# TrinketTrigger.net
KiCad netlist of a schematic drawn in EAGLE
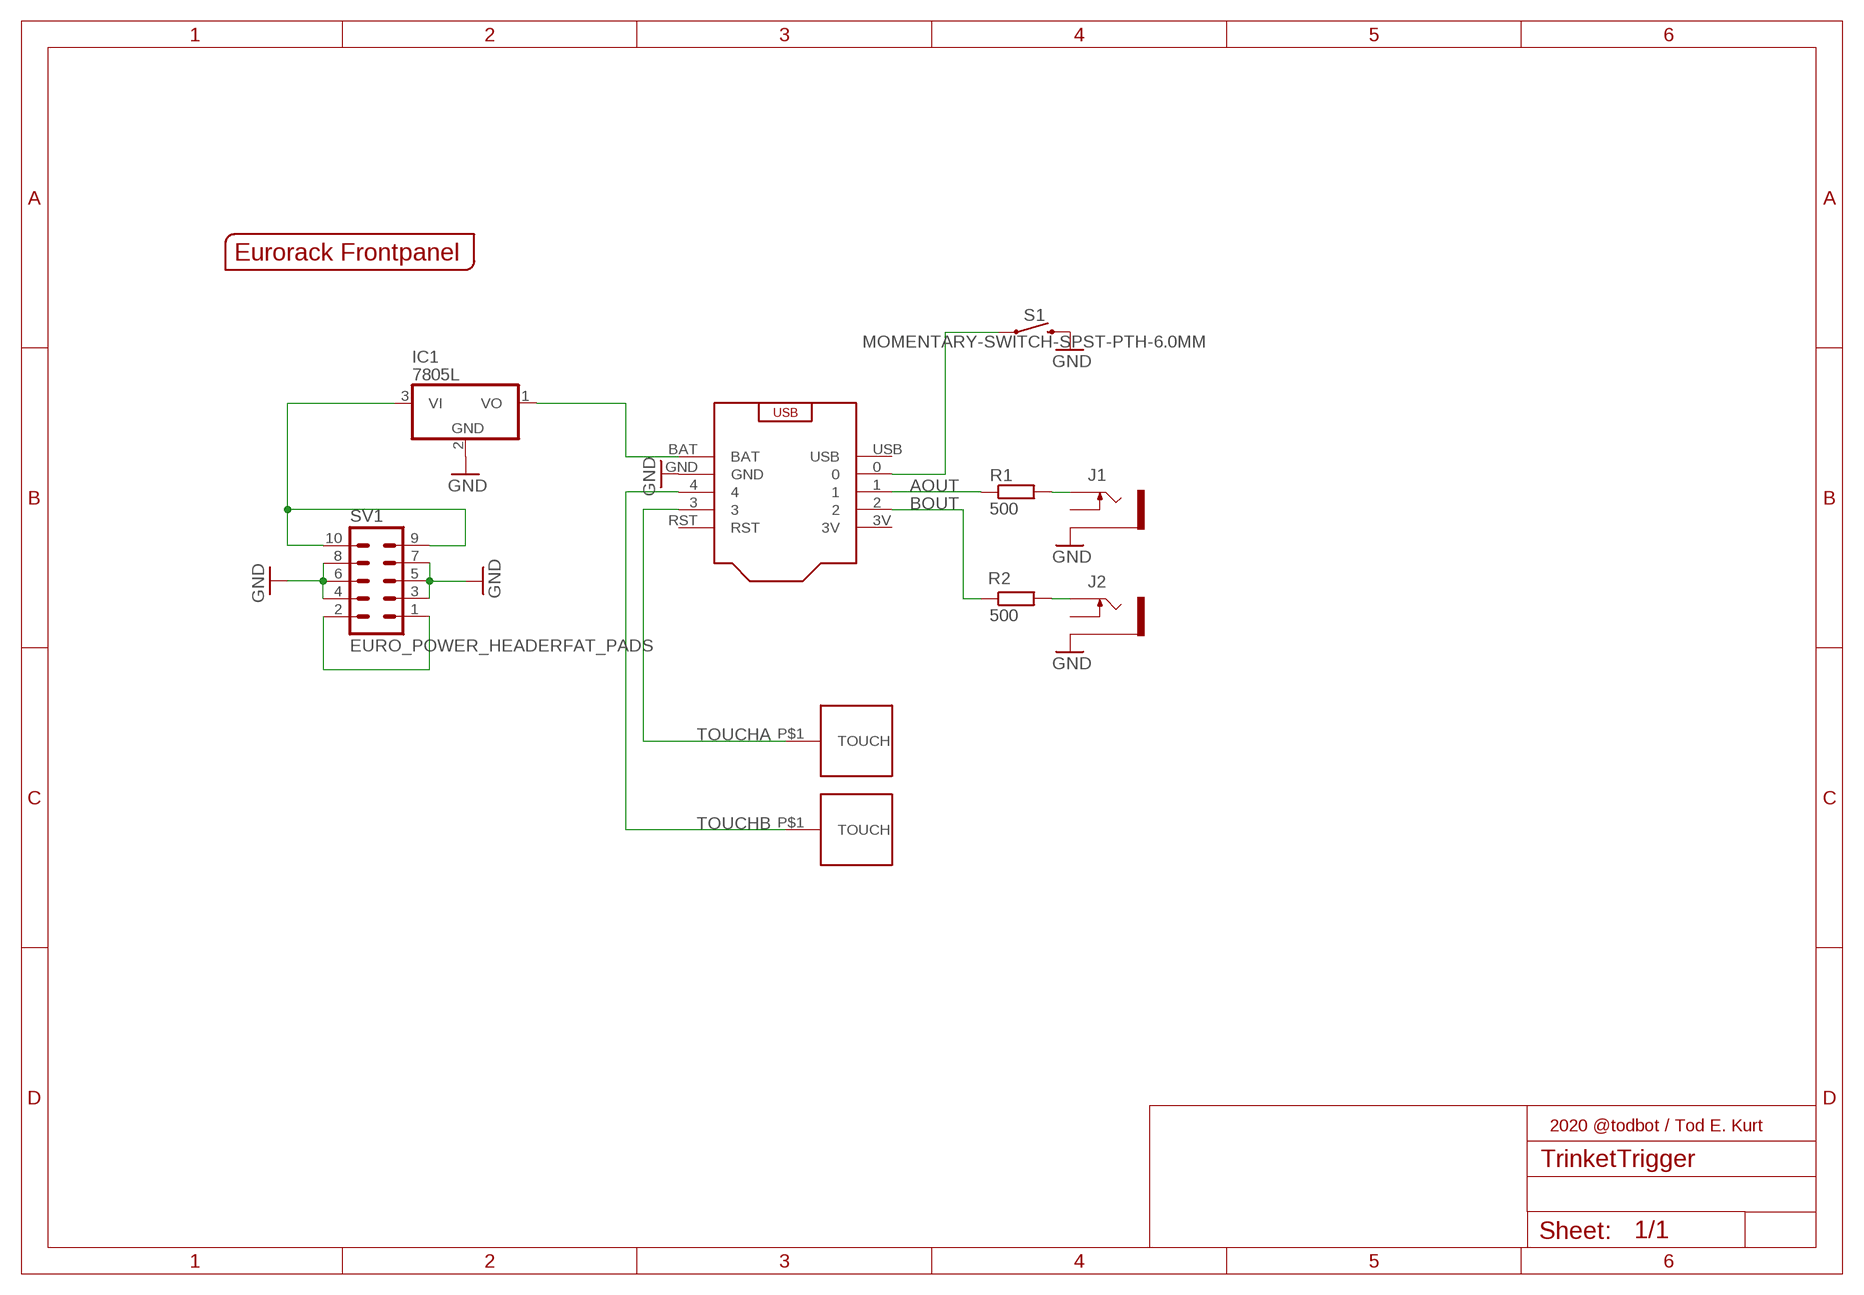
[diagram p0: schematic, sheet 1]

(export (version "E")
  (design (tool "Eeschema 10.0.6"))
  (components
    (comp (ref "IC1")
      (value "7805L")
      (footprint "eagle-import:TO92")
      (libsource (lib "eagle-import") (part "78L05"))
    )
    (comp (ref "J1")
      (value "THONKICONNNEW")
      (footprint "eagle-import:WQP-PJ301M-12_JACK")
      (libsource (lib "eagle-import") (part "THONKICONNNEW"))
    )
    (comp (ref "J2")
      (value "THONKICONNNEW")
      (footprint "eagle-import:WQP-PJ301M-12_JACK")
      (libsource (lib "eagle-import") (part "THONKICONNNEW"))
    )
    (comp (ref "R1")
      (value "500")
      (footprint "eagle-import:0204_7")
      (libsource (lib "eagle-import") (part "R-EU_0204/7"))
    )
    (comp (ref "R2")
      (value "500")
      (footprint "eagle-import:0204_7")
      (libsource (lib "eagle-import") (part "R-EU_0204/7"))
    )
    (comp (ref "S1")
      (value "MOMENTARY-SWITCH-SPST-PTH-6.0MM")
      (footprint "eagle-import:TACTILE_SWITCH_PTH_6.0MM")
      (libsource (lib "eagle-import") (part "MOMENTARY-SWITCH-SPST-PTH-6.0MM"))
    )
    (comp (ref "SV1")
      (value "EURO_POWER_HEADERFAT_PADS")
      (footprint "eagle-import:EURO_PWR_HEADER_FAT")
      (libsource (lib "eagle-import") (part "EURO_POWER_HEADERFAT_PADS"))
    )
    (comp (ref "TOUCHA")
      (value "TOUCHPADA")
      (footprint "eagle-import:TOUCHPADA")
      (libsource (lib "eagle-import") (part "TOUCHPADA"))
    )
    (comp (ref "TOUCHB")
      (value "TOUCHPADA")
      (footprint "eagle-import:TOUCHPADA")
      (libsource (lib "eagle-import") (part "TOUCHPADA"))
    )
    (comp (ref "U$1")
      (value "EURORACK_PANEL6HP")
      (footprint "eagle-import:EURORACK6HPPANEL")
      (libsource (lib "eagle-import") (part "EURORACK_PANEL6HP"))
    )
    (comp (ref "U$2")
      (value "TRINKETM0NH")
      (footprint "eagle-import:TRINKETMO_NOHOLES")
      (libsource (lib "eagle-import") (part "TRINKETM0NH"))
    )
  )
  (nets
    (net (code "1") (name "/AOUT") (class "Default")
      (node (ref "R1") (pin "1") (pinfunction "1_1") (pintype "passive"))
      (node (ref "U$2") (pin "1") (pinfunction "1_1") (pintype "bidirectional"))
    )
    (net (code "2") (name "/BOUT") (class "Default")
      (node (ref "R2") (pin "1") (pinfunction "1_1") (pintype "passive"))
      (node (ref "U$2") (pin "2") (pinfunction "2_2") (pintype "bidirectional"))
    )
    (net (code "3") (name "/TOUCHA") (class "Default")
      (node (ref "TOUCHA") (pin "P$1") (pinfunction "TOUCH_P$1") (pintype "bidirectional"))
      (node (ref "U$2") (pin "3") (pinfunction "3_3") (pintype "bidirectional"))
    )
    (net (code "4") (name "/TOUCHB") (class "Default")
      (node (ref "TOUCHB") (pin "P$1") (pinfunction "TOUCH_P$1") (pintype "bidirectional"))
      (node (ref "U$2") (pin "4") (pinfunction "4_4") (pintype "bidirectional"))
    )
    (net (code "5") (name "GND") (class "Default")
      (node (ref "IC1") (pin "2") (pinfunction "GND_2") (pintype "passive"))
      (node (ref "J1") (pin "P$3_SLEEVE") (pinfunction "SLEEVE_P$3_SLEEVE") (pintype "passive"))
      (node (ref "J2") (pin "P$3_SLEEVE") (pinfunction "SLEEVE_P$3_SLEEVE") (pintype "passive"))
      (node (ref "S1") (pin "3") (pinfunction "2_3") (pintype "passive"))
      (node (ref "SV1") (pin "3") (pinfunction "3_3") (pintype "passive"))
      (node (ref "SV1") (pin "4") (pinfunction "4_4") (pintype "passive"))
      (node (ref "SV1") (pin "5") (pinfunction "5_5") (pintype "passive"))
      (node (ref "SV1") (pin "6") (pinfunction "6_6") (pintype "passive"))
      (node (ref "SV1") (pin "7") (pinfunction "7_7") (pintype "passive"))
      (node (ref "SV1") (pin "8") (pinfunction "8_8") (pintype "passive"))
      (node (ref "U$2") (pin "GND") (pinfunction "GND_GND") (pintype "bidirectional"))
    )
    (net (code "6") (name "Net-(IC1-VI)") (class "Default")
      (node (ref "IC1") (pin "3") (pinfunction "VI_3") (pintype "input"))
      (node (ref "SV1") (pin "10") (pinfunction "10_10") (pintype "passive"))
      (node (ref "SV1") (pin "9") (pinfunction "9_9") (pintype "passive"))
    )
    (net (code "7") (name "Net-(IC1-VO)") (class "Default")
      (node (ref "IC1") (pin "1") (pinfunction "VO_1") (pintype "passive"))
      (node (ref "U$2") (pin "BAT") (pinfunction "BAT_BAT") (pintype "bidirectional"))
    )
    (net (code "8") (name "Net-(J1-TIP)") (class "Default")
      (node (ref "J1") (pin "P$1_TIP") (pinfunction "TIP_P$1_TIP") (pintype "passive"))
      (node (ref "R1") (pin "2") (pinfunction "2_2") (pintype "passive"))
    )
    (net (code "9") (name "Net-(J2-TIP)") (class "Default")
      (node (ref "J2") (pin "P$1_TIP") (pinfunction "TIP_P$1_TIP") (pintype "passive"))
      (node (ref "R2") (pin "2") (pinfunction "2_2") (pintype "passive"))
    )
    (net (code "10") (name "Net-(S1-Pad1)") (class "Default")
      (node (ref "S1") (pin "1") (pinfunction "1_1") (pintype "passive"))
      (node (ref "U$2") (pin "0") (pinfunction "0_0") (pintype "bidirectional"))
    )
    (net (code "11") (name "Net-(SV1-Pad1)") (class "Default")
      (node (ref "SV1") (pin "1") (pinfunction "1_1") (pintype "passive"))
      (node (ref "SV1") (pin "2") (pinfunction "2_2") (pintype "passive"))
    )
    (net (code "12") (name "unconnected-(J1-SWITCH-PadP$2_SWITCH)") (class "Default")
      (node (ref "J1") (pin "P$2_SWITCH") (pinfunction "SWITCH_P$2_SWITCH") (pintype "passive"))
    )
    (net (code "13") (name "unconnected-(J2-SWITCH-PadP$2_SWITCH)") (class "Default")
      (node (ref "J2") (pin "P$2_SWITCH") (pinfunction "SWITCH_P$2_SWITCH") (pintype "passive"))
    )
    (net (code "14") (name "unconnected-(U$2-Pad3V)") (class "Default")
      (node (ref "U$2") (pin "3V") (pinfunction "3V_3V") (pintype "bidirectional"))
    )
    (net (code "15") (name "unconnected-(U$2-PadRST)") (class "Default")
      (node (ref "U$2") (pin "RST") (pinfunction "RST_RST") (pintype "bidirectional"))
    )
    (net (code "16") (name "unconnected-(U$2-PadUSB)") (class "Default")
      (node (ref "U$2") (pin "USB") (pinfunction "USB_USB") (pintype "bidirectional"))
    )
  )
)
